# Alarm_clock.net
KiCad netlist of a schematic drawn in EAGLE
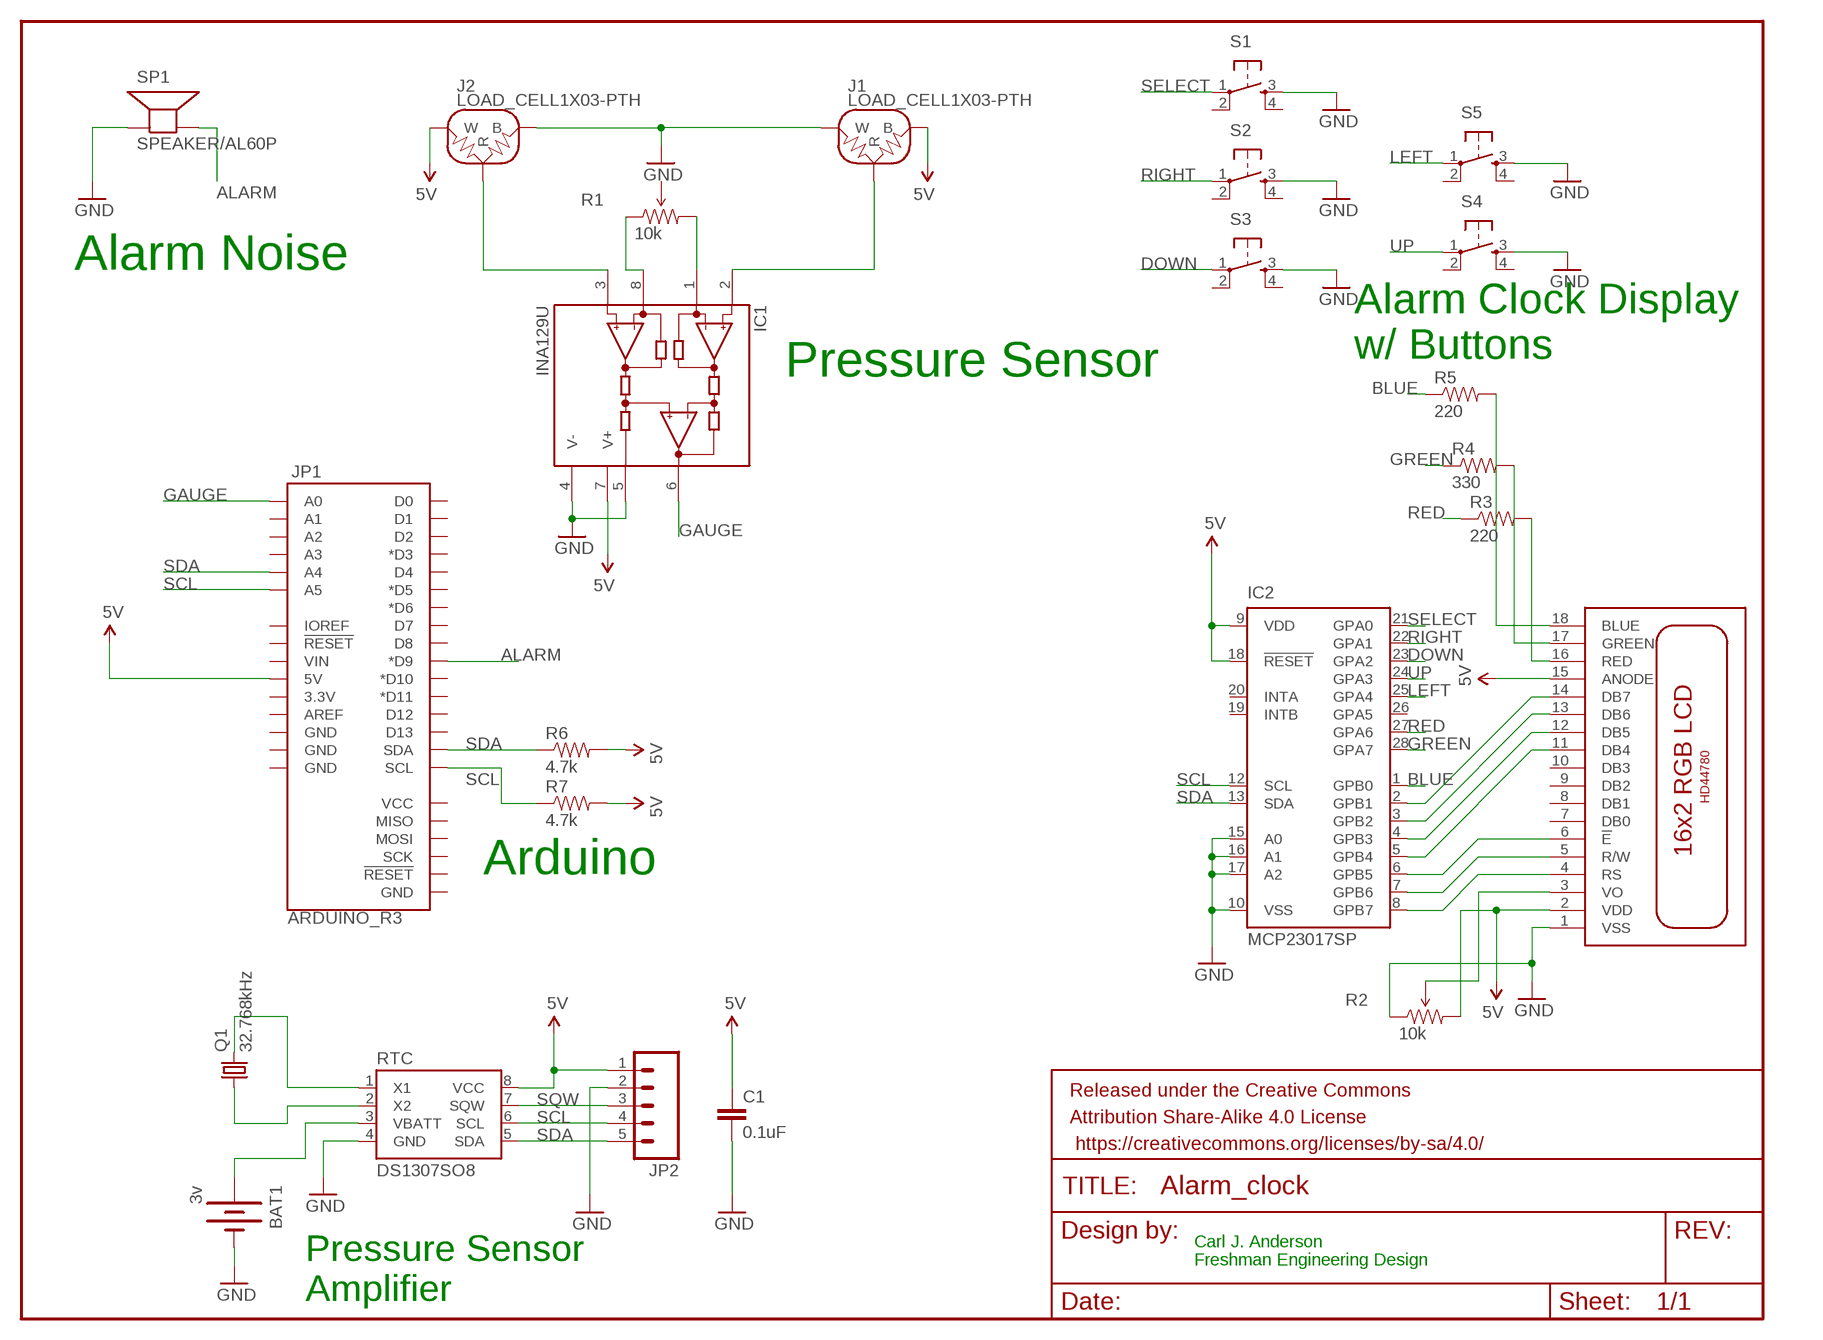
[diagram p0: schematic, sheet 1]

(export (version "E")
  (design (tool "Eeschema 10.0.6"))
  (components
    (comp (ref "BAT1")
      (value "3v")
      (footprint "eagle-import:BATTERY_20MM_PTH_COMPACT")
      (libsource (lib "eagle-import") (part "BATTERYFOB"))
    )
    (comp (ref "C1")
      (value "0.1uF")
      (footprint "eagle-import:0402-CAP")
      (libsource (lib "eagle-import") (part "0.1UF-16V(+-10%)(0402)"))
    )
    (comp (ref "FRAME1")
      (value "FRAME-LETTER")
      (footprint "eagle-import:CREATIVE_COMMONS")
      (libsource (lib "eagle-import") (part "FRAME-LETTER"))
    )
    (comp (ref "IC1")
      (value "INA129U")
      (footprint "eagle-import:SO08")
      (fields (field (name "MF") "TEXAS INSTRUMENTS"))
      (libsource (lib "eagle-import") (part "INA129U"))
    )
    (comp (ref "IC2")
      (value "MCP23017SP")
      (footprint "eagle-import:DIL28-3")
      (fields (field (name "MF") "MICROCHIP") (field (name "MPN") "MCP23017-E/SP"))
      (libsource (lib "eagle-import") (part "MCP23017SP"))
    )
    (comp (ref "J1")
      (value "LOAD_CELL1X03-PTH")
      (footprint "eagle-import:1X03")
      (libsource (lib "eagle-import") (part "LOAD_CELL1X03-PTH"))
    )
    (comp (ref "J2")
      (value "LOAD_CELL1X03-PTH")
      (footprint "eagle-import:1X03")
      (libsource (lib "eagle-import") (part "LOAD_CELL1X03-PTH"))
    )
    (comp (ref "JP1")
      (value "ARDUINO_R3")
      (footprint "eagle-import:ARDUINO_R3")
      (libsource (lib "eagle-import") (part "ARDUINO_R3"))
    )
    (comp (ref "JP2")
      (value "M05PTH")
      (footprint "eagle-import:1X05")
      (libsource (lib "eagle-import") (part "M05PTH"))
    )
    (comp (ref "Q1")
      (value "32.768kHz")
      (footprint "eagle-import:TC26H")
      (libsource (lib "eagle-import") (part "CRYSTALTC26H"))
    )
    (comp (ref "R1")
      (value "10k")
      (footprint "eagle-import:TRIMPOT-5MM-V2")
      (libsource (lib "eagle-import") (part "TRIMPOT"))
    )
    (comp (ref "R2")
      (value "10k")
      (footprint "eagle-import:TRIMPOT-5MM-V2")
      (libsource (lib "eagle-import") (part "TRIMPOT"))
    )
    (comp (ref "R3")
      (value "220")
      (footprint "eagle-import:AXIAL-0.4")
      (libsource (lib "eagle-import") (part "RESISTORPTH-1/4W"))
    )
    (comp (ref "R4")
      (value "330")
      (footprint "eagle-import:AXIAL-0.4")
      (libsource (lib "eagle-import") (part "RESISTORPTH-1/4W"))
    )
    (comp (ref "R5")
      (value "220")
      (footprint "eagle-import:AXIAL-0.4")
      (libsource (lib "eagle-import") (part "RESISTORPTH-1/4W"))
    )
    (comp (ref "R6")
      (value "4.7k")
      (footprint "eagle-import:AXIAL-0.4")
      (libsource (lib "eagle-import") (part "RESISTORPTH-1/4W"))
    )
    (comp (ref "R7")
      (value "4.7k")
      (footprint "eagle-import:AXIAL-0.4")
      (libsource (lib "eagle-import") (part "RESISTORPTH-1/4W"))
    )
    (comp (ref "RTC")
      (value "DS1307SO8")
      (footprint "eagle-import:SO08")
      (libsource (lib "eagle-import") (part "DS1307SO8"))
    )
    (comp (ref "S1")
      (value "TAC_SWITCHPTH")
      (footprint "eagle-import:TACTILE-PTH")
      (libsource (lib "eagle-import") (part "TAC_SWITCHPTH"))
    )
    (comp (ref "S2")
      (value "TAC_SWITCHPTH")
      (footprint "eagle-import:TACTILE-PTH")
      (libsource (lib "eagle-import") (part "TAC_SWITCHPTH"))
    )
    (comp (ref "S3")
      (value "TAC_SWITCHPTH")
      (footprint "eagle-import:TACTILE-PTH")
      (libsource (lib "eagle-import") (part "TAC_SWITCHPTH"))
    )
    (comp (ref "S4")
      (value "TAC_SWITCHPTH")
      (footprint "eagle-import:TACTILE-PTH")
      (libsource (lib "eagle-import") (part "TAC_SWITCHPTH"))
    )
    (comp (ref "S5")
      (value "TAC_SWITCHPTH")
      (footprint "eagle-import:TACTILE-PTH")
      (libsource (lib "eagle-import") (part "TAC_SWITCHPTH"))
    )
    (comp (ref "SP1")
      (value "SPEAKER/AL60P")
      (footprint "eagle-import:AL60P")
      (libsource (lib "eagle-import") (part "SPEAKER/AL60P"))
    )
    (comp (ref "U$1")
      (value "LCD16X2-RGB")
      (footprint "eagle-import:LCD16X2-RGB")
      (libsource (lib "eagle-import") (part "LCD16X2-RGB"))
    )
  )
  (nets
    (net (code "1") (name "/ALARM") (class "Default")
      (node (ref "JP1") (pin "D9") (pinfunction "*D9_D9") (pintype "bidirectional"))
      (node (ref "SP1") (pin "2") (pinfunction "-_2") (pintype "passive"))
    )
    (net (code "2") (name "/BLUE") (class "Default")
      (node (ref "IC2") (pin "1") (pinfunction "GPB0_1") (pintype "bidirectional"))
      (node (ref "R5") (pin "P$1") (pinfunction "1_P$1") (pintype "passive"))
    )
    (net (code "3") (name "/DOWN") (class "Default")
      (node (ref "IC2") (pin "23") (pinfunction "GPA2_23") (pintype "bidirectional"))
      (node (ref "S3") (pin "1") (pinfunction "1_1") (pintype "passive"))
    )
    (net (code "4") (name "/GAUGE") (class "Default")
      (node (ref "IC1") (pin "6") (pinfunction "OUT_6") (pintype "output"))
      (node (ref "JP1") (pin "A0") (pinfunction "A0_A0") (pintype "bidirectional"))
    )
    (net (code "5") (name "/GREEN") (class "Default")
      (node (ref "IC2") (pin "28") (pinfunction "GPA7_28") (pintype "bidirectional"))
      (node (ref "R4") (pin "P$1") (pinfunction "1_P$1") (pintype "passive"))
    )
    (net (code "6") (name "/LEFT") (class "Default")
      (node (ref "IC2") (pin "25") (pinfunction "GPA4_25") (pintype "bidirectional"))
      (node (ref "S5") (pin "1") (pinfunction "1_1") (pintype "passive"))
    )
    (net (code "7") (name "/RED") (class "Default")
      (node (ref "IC2") (pin "27") (pinfunction "GPA6_27") (pintype "bidirectional"))
      (node (ref "R3") (pin "P$1") (pinfunction "1_P$1") (pintype "passive"))
    )
    (net (code "8") (name "/RIGHT") (class "Default")
      (node (ref "IC2") (pin "22") (pinfunction "GPA1_22") (pintype "bidirectional"))
      (node (ref "S2") (pin "1") (pinfunction "1_1") (pintype "passive"))
    )
    (net (code "9") (name "/SCL") (class "Default")
      (node (ref "IC2") (pin "12") (pinfunction "SCL_12") (pintype "input"))
      (node (ref "JP1") (pin "A5") (pinfunction "A5_A5") (pintype "bidirectional"))
      (node (ref "JP1") (pin "SCL") (pinfunction "SCL_SCL") (pintype "bidirectional"))
      (node (ref "JP2") (pin "4") (pinfunction "4_4") (pintype "passive"))
      (node (ref "R7") (pin "P$1") (pinfunction "1_P$1") (pintype "passive"))
      (node (ref "RTC") (pin "6") (pinfunction "SCL_6") (pintype "bidirectional"))
    )
    (net (code "10") (name "/SDA") (class "Default")
      (node (ref "IC2") (pin "13") (pinfunction "SDA_13") (pintype "bidirectional"))
      (node (ref "JP1") (pin "A4") (pinfunction "A4_A4") (pintype "bidirectional"))
      (node (ref "JP1") (pin "SDA") (pinfunction "SDA_SDA") (pintype "bidirectional"))
      (node (ref "JP2") (pin "5") (pinfunction "5_5") (pintype "passive"))
      (node (ref "R6") (pin "P$1") (pinfunction "1_P$1") (pintype "passive"))
      (node (ref "RTC") (pin "5") (pinfunction "SDA_5") (pintype "bidirectional"))
    )
    (net (code "11") (name "/SELECT") (class "Default")
      (node (ref "IC2") (pin "21") (pinfunction "GPA0_21") (pintype "bidirectional"))
      (node (ref "S1") (pin "1") (pinfunction "1_1") (pintype "passive"))
    )
    (net (code "12") (name "/SQW") (class "Default")
      (node (ref "JP2") (pin "3") (pinfunction "3_3") (pintype "passive"))
      (node (ref "RTC") (pin "7") (pinfunction "SQW_7") (pintype "bidirectional"))
    )
    (net (code "13") (name "/UP") (class "Default")
      (node (ref "IC2") (pin "24") (pinfunction "GPA3_24") (pintype "bidirectional"))
      (node (ref "S4") (pin "1") (pinfunction "1_1") (pintype "passive"))
    )
    (net (code "14") (name "5V") (class "Default")
      (node (ref "C1") (pin "1") (pinfunction "1_1") (pintype "passive"))
      (node (ref "IC1") (pin "7") (pinfunction "V+_7") (pintype "power_in"))
      (node (ref "IC2") (pin "18") (pinfunction "~{RESET}_18") (pintype "input"))
      (node (ref "IC2") (pin "9") (pinfunction "VDD_9") (pintype "power_in"))
      (node (ref "J1") (pin "1") (pinfunction "B_1") (pintype "passive"))
      (node (ref "J2") (pin "2") (pinfunction "W_2") (pintype "passive"))
      (node (ref "JP1") (pin "5V") (pinfunction "5V_5V") (pintype "bidirectional"))
      (node (ref "JP2") (pin "1") (pinfunction "1_1") (pintype "passive"))
      (node (ref "R2") (pin "C") (pinfunction "CW_C") (pintype "passive"))
      (node (ref "R6") (pin "P$2") (pinfunction "2_P$2") (pintype "passive"))
      (node (ref "R7") (pin "P$2") (pinfunction "2_P$2") (pintype "passive"))
      (node (ref "RTC") (pin "8") (pinfunction "VCC_8") (pintype "bidirectional"))
      (node (ref "U$1") (pin "15") (pinfunction "ANODE_15") (pintype "bidirectional"))
      (node (ref "U$1") (pin "2") (pinfunction "VDD_2") (pintype "bidirectional"))
    )
    (net (code "15") (name "GND") (class "Default")
      (node (ref "BAT1") (pin "2") (pinfunction "-_2") (pintype "power_in"))
      (node (ref "C1") (pin "2") (pinfunction "2_2") (pintype "passive"))
      (node (ref "IC1") (pin "4") (pinfunction "V-_4") (pintype "power_in"))
      (node (ref "IC1") (pin "5") (pinfunction "REF_5") (pintype "passive"))
      (node (ref "IC2") (pin "10") (pinfunction "VSS_10") (pintype "power_in"))
      (node (ref "IC2") (pin "15") (pinfunction "A0_15") (pintype "input"))
      (node (ref "IC2") (pin "16") (pinfunction "A1_16") (pintype "input"))
      (node (ref "IC2") (pin "17") (pinfunction "A2_17") (pintype "input"))
      (node (ref "J1") (pin "2") (pinfunction "W_2") (pintype "passive"))
      (node (ref "J2") (pin "1") (pinfunction "B_1") (pintype "passive"))
      (node (ref "JP2") (pin "2") (pinfunction "2_2") (pintype "passive"))
      (node (ref "R2") (pin "A") (pinfunction "CCW_A") (pintype "passive"))
      (node (ref "RTC") (pin "4") (pinfunction "GND_4") (pintype "bidirectional"))
      (node (ref "S1") (pin "3") (pinfunction "3_3") (pintype "passive"))
      (node (ref "S2") (pin "3") (pinfunction "3_3") (pintype "passive"))
      (node (ref "S3") (pin "3") (pinfunction "3_3") (pintype "passive"))
      (node (ref "S4") (pin "3") (pinfunction "3_3") (pintype "passive"))
      (node (ref "S5") (pin "3") (pinfunction "3_3") (pintype "passive"))
      (node (ref "SP1") (pin "1") (pinfunction "+_1") (pintype "passive"))
      (node (ref "U$1") (pin "1") (pinfunction "VSS_1") (pintype "bidirectional"))
    )
    (net (code "16") (name "Net-(BAT1-+)") (class "Default")
      (node (ref "BAT1") (pin "1") (pinfunction "+_1") (pintype "power_in"))
      (node (ref "RTC") (pin "3") (pinfunction "VBATT_3") (pintype "bidirectional"))
    )
    (net (code "17") (name "Net-(IC1-+IN)") (class "Default")
      (node (ref "IC1") (pin "3") (pinfunction "+IN_3") (pintype "input"))
      (node (ref "J2") (pin "3") (pinfunction "R_3") (pintype "passive"))
    )
    (net (code "18") (name "Net-(IC1--IN)") (class "Default")
      (node (ref "IC1") (pin "2") (pinfunction "-IN_2") (pintype "input"))
      (node (ref "J1") (pin "3") (pinfunction "R_3") (pintype "passive"))
    )
    (net (code "19") (name "Net-(IC2-GPB1)") (class "Default")
      (node (ref "IC2") (pin "2") (pinfunction "GPB1_2") (pintype "bidirectional"))
      (node (ref "U$1") (pin "14") (pinfunction "DB7_14") (pintype "bidirectional"))
    )
    (net (code "20") (name "Net-(IC2-GPB2)") (class "Default")
      (node (ref "IC2") (pin "3") (pinfunction "GPB2_3") (pintype "bidirectional"))
      (node (ref "U$1") (pin "13") (pinfunction "DB6_13") (pintype "bidirectional"))
    )
    (net (code "21") (name "Net-(IC2-GPB3)") (class "Default")
      (node (ref "IC2") (pin "4") (pinfunction "GPB3_4") (pintype "bidirectional"))
      (node (ref "U$1") (pin "12") (pinfunction "DB5_12") (pintype "bidirectional"))
    )
    (net (code "22") (name "Net-(IC2-GPB4)") (class "Default")
      (node (ref "IC2") (pin "5") (pinfunction "GPB4_5") (pintype "bidirectional"))
      (node (ref "U$1") (pin "11") (pinfunction "DB4_11") (pintype "bidirectional"))
    )
    (net (code "23") (name "Net-(IC2-GPB5)") (class "Default")
      (node (ref "IC2") (pin "6") (pinfunction "GPB5_6") (pintype "bidirectional"))
      (node (ref "U$1") (pin "6") (pinfunction "~{E}_6") (pintype "bidirectional"))
    )
    (net (code "24") (name "Net-(IC2-GPB6)") (class "Default")
      (node (ref "IC2") (pin "7") (pinfunction "GPB6_7") (pintype "bidirectional"))
      (node (ref "U$1") (pin "5") (pinfunction "R/W_5") (pintype "bidirectional"))
    )
    (net (code "25") (name "Net-(IC2-GPB7)") (class "Default")
      (node (ref "IC2") (pin "8") (pinfunction "GPB7_8") (pintype "bidirectional"))
      (node (ref "U$1") (pin "4") (pinfunction "RS_4") (pintype "bidirectional"))
    )
    (net (code "26") (name "Net-(R1-CCW)") (class "Default")
      (node (ref "IC1") (pin "8") (pinfunction "RG_8") (pintype "passive"))
      (node (ref "R1") (pin "A") (pinfunction "CCW_A") (pintype "passive"))
    )
    (net (code "27") (name "Net-(R1-CW)") (class "Default")
      (node (ref "IC1") (pin "1") (pinfunction "RG_1") (pintype "passive"))
      (node (ref "R1") (pin "C") (pinfunction "CW_C") (pintype "passive"))
    )
    (net (code "28") (name "Net-(R2-WIPER)") (class "Default")
      (node (ref "R2") (pin "B") (pinfunction "WIPER_B") (pintype "passive"))
      (node (ref "U$1") (pin "3") (pinfunction "VO_3") (pintype "bidirectional"))
    )
    (net (code "29") (name "Net-(R3-2)") (class "Default")
      (node (ref "R3") (pin "P$2") (pinfunction "2_P$2") (pintype "passive"))
      (node (ref "U$1") (pin "16") (pinfunction "RED_16") (pintype "bidirectional"))
    )
    (net (code "30") (name "Net-(R4-2)") (class "Default")
      (node (ref "R4") (pin "P$2") (pinfunction "2_P$2") (pintype "passive"))
      (node (ref "U$1") (pin "17") (pinfunction "GREEN_17") (pintype "bidirectional"))
    )
    (net (code "31") (name "Net-(R5-2)") (class "Default")
      (node (ref "R5") (pin "P$2") (pinfunction "2_P$2") (pintype "passive"))
      (node (ref "U$1") (pin "18") (pinfunction "BLUE_18") (pintype "bidirectional"))
    )
    (net (code "32") (name "Net-(RTC-X1)") (class "Default")
      (node (ref "Q1") (pin "2") (pinfunction "2_2") (pintype "passive"))
      (node (ref "RTC") (pin "1") (pinfunction "X1_1") (pintype "bidirectional"))
    )
    (net (code "33") (name "Net-(RTC-X2)") (class "Default")
      (node (ref "Q1") (pin "1") (pinfunction "1_1") (pintype "passive"))
      (node (ref "RTC") (pin "2") (pinfunction "X2_2") (pintype "bidirectional"))
    )
    (net (code "34") (name "unconnected-(IC2-GPA5-Pad26)") (class "Default")
      (node (ref "IC2") (pin "26") (pinfunction "GPA5_26") (pintype "bidirectional"))
    )
    (net (code "35") (name "unconnected-(IC2-INTA-Pad20)") (class "Default")
      (node (ref "IC2") (pin "20") (pinfunction "INTA_20") (pintype "output"))
    )
    (net (code "36") (name "unconnected-(IC2-INTB-Pad19)") (class "Default")
      (node (ref "IC2") (pin "19") (pinfunction "INTB_19") (pintype "output"))
    )
    (net (code "37") (name "unconnected-(JP1-*D3-PadD3)") (class "Default")
      (node (ref "JP1") (pin "D3") (pinfunction "*D3_D3") (pintype "bidirectional"))
    )
    (net (code "38") (name "unconnected-(JP1-*D5-PadD5)") (class "Default")
      (node (ref "JP1") (pin "D5") (pinfunction "*D5_D5") (pintype "bidirectional"))
    )
    (net (code "39") (name "unconnected-(JP1-*D6-PadD6)") (class "Default")
      (node (ref "JP1") (pin "D6") (pinfunction "*D6_D6") (pintype "bidirectional"))
    )
    (net (code "40") (name "unconnected-(JP1-*D10-PadD10)") (class "Default")
      (node (ref "JP1") (pin "D10") (pinfunction "*D10_D10") (pintype "bidirectional"))
    )
    (net (code "41") (name "unconnected-(JP1-*D11-PadD11)") (class "Default")
      (node (ref "JP1") (pin "D11") (pinfunction "*D11_D11") (pintype "bidirectional"))
    )
    (net (code "42") (name "unconnected-(JP1-GND-PadGND@1)") (class "Default")
      (node (ref "JP1") (pin "GND@1") (pinfunction "GND_GND@1") (pintype "bidirectional"))
    )
    (net (code "43") (name "unconnected-(JP1-GND-PadGND@2)") (class "Default")
      (node (ref "JP1") (pin "GND@2") (pinfunction "GND_GND@2") (pintype "bidirectional"))
    )
    (net (code "44") (name "unconnected-(JP1-GND-PadGND@3)") (class "Default")
      (node (ref "JP1") (pin "GND@3") (pinfunction "GND_GND@3") (pintype "bidirectional"))
    )
    (net (code "45") (name "unconnected-(JP1-GND-PadGND@4)") (class "Default")
      (node (ref "JP1") (pin "GND@4") (pinfunction "GND_GND@4") (pintype "bidirectional"))
    )
    (net (code "46") (name "unconnected-(JP1-Pad3.3V)") (class "Default")
      (node (ref "JP1") (pin "3.3V") (pinfunction "3.3V_3.3V") (pintype "bidirectional"))
    )
    (net (code "47") (name "unconnected-(JP1-PadA1)") (class "Default")
      (node (ref "JP1") (pin "A1") (pinfunction "A1_A1") (pintype "bidirectional"))
    )
    (net (code "48") (name "unconnected-(JP1-PadA2)") (class "Default")
      (node (ref "JP1") (pin "A2") (pinfunction "A2_A2") (pintype "bidirectional"))
    )
    (net (code "49") (name "unconnected-(JP1-PadA3)") (class "Default")
      (node (ref "JP1") (pin "A3") (pinfunction "A3_A3") (pintype "bidirectional"))
    )
    (net (code "50") (name "unconnected-(JP1-PadAREF)") (class "Default")
      (node (ref "JP1") (pin "AREF") (pinfunction "AREF_AREF") (pintype "bidirectional"))
    )
    (net (code "51") (name "unconnected-(JP1-PadD0)") (class "Default")
      (node (ref "JP1") (pin "D0") (pinfunction "D0_D0") (pintype "bidirectional"))
    )
    (net (code "52") (name "unconnected-(JP1-PadD1)") (class "Default")
      (node (ref "JP1") (pin "D1") (pinfunction "D1_D1") (pintype "bidirectional"))
    )
    (net (code "53") (name "unconnected-(JP1-PadD2)") (class "Default")
      (node (ref "JP1") (pin "D2") (pinfunction "D2_D2") (pintype "bidirectional"))
    )
    (net (code "54") (name "unconnected-(JP1-PadD4)") (class "Default")
      (node (ref "JP1") (pin "D4") (pinfunction "D4_D4") (pintype "bidirectional"))
    )
    (net (code "55") (name "unconnected-(JP1-PadD7)") (class "Default")
      (node (ref "JP1") (pin "D7") (pinfunction "D7_D7") (pintype "bidirectional"))
    )
    (net (code "56") (name "unconnected-(JP1-PadD8)") (class "Default")
      (node (ref "JP1") (pin "D8") (pinfunction "D8_D8") (pintype "bidirectional"))
    )
    (net (code "57") (name "unconnected-(JP1-PadD12)") (class "Default")
      (node (ref "JP1") (pin "D12") (pinfunction "D12_D12") (pintype "bidirectional"))
    )
    (net (code "58") (name "unconnected-(JP1-PadD13)") (class "Default")
      (node (ref "JP1") (pin "D13") (pinfunction "D13_D13") (pintype "bidirectional"))
    )
    (net (code "59") (name "unconnected-(JP1-PadIOREF)") (class "Default")
      (node (ref "JP1") (pin "IOREF") (pinfunction "IOREF_IOREF") (pintype "bidirectional"))
    )
    (net (code "60") (name "unconnected-(JP1-PadMISO)") (class "Default")
      (node (ref "JP1") (pin "MISO") (pinfunction "MISO_MISO") (pintype "bidirectional"))
    )
    (net (code "61") (name "unconnected-(JP1-PadMOSI)") (class "Default")
      (node (ref "JP1") (pin "MOSI") (pinfunction "MOSI_MOSI") (pintype "bidirectional"))
    )
    (net (code "62") (name "unconnected-(JP1-PadSCK)") (class "Default")
      (node (ref "JP1") (pin "SCK") (pinfunction "SCK_SCK") (pintype "bidirectional"))
    )
    (net (code "63") (name "unconnected-(JP1-PadVCC)") (class "Default")
      (node (ref "JP1") (pin "VCC") (pinfunction "VCC_VCC") (pintype "bidirectional"))
    )
    (net (code "64") (name "unconnected-(JP1-PadVIN)") (class "Default")
      (node (ref "JP1") (pin "VIN") (pinfunction "VIN_VIN") (pintype "bidirectional"))
    )
    (net (code "65") (name "unconnected-(JP1-~{RESET}-PadRESET@1)") (class "Default")
      (node (ref "JP1") (pin "RESET@1") (pinfunction "~{RESET}_RESET@1") (pintype "bidirectional"))
    )
    (net (code "66") (name "unconnected-(JP1-~{RESET}-PadRESET@2)") (class "Default")
      (node (ref "JP1") (pin "RESET@2") (pinfunction "~{RESET}_RESET@2") (pintype "bidirectional"))
    )
    (net (code "67") (name "unconnected-(R1-WIPER-PadB)") (class "Default")
      (node (ref "R1") (pin "B") (pinfunction "WIPER_B") (pintype "passive"))
    )
    (net (code "68") (name "unconnected-(S1-Pad2)") (class "Default")
      (node (ref "S1") (pin "2") (pinfunction "2_2") (pintype "passive"))
    )
    (net (code "69") (name "unconnected-(S1-Pad4)") (class "Default")
      (node (ref "S1") (pin "4") (pinfunction "4_4") (pintype "passive"))
    )
    (net (code "70") (name "unconnected-(S2-Pad2)") (class "Default")
      (node (ref "S2") (pin "2") (pinfunction "2_2") (pintype "passive"))
    )
    (net (code "71") (name "unconnected-(S2-Pad4)") (class "Default")
      (node (ref "S2") (pin "4") (pinfunction "4_4") (pintype "passive"))
    )
    (net (code "72") (name "unconnected-(S3-Pad2)") (class "Default")
      (node (ref "S3") (pin "2") (pinfunction "2_2") (pintype "passive"))
    )
    (net (code "73") (name "unconnected-(S3-Pad4)") (class "Default")
      (node (ref "S3") (pin "4") (pinfunction "4_4") (pintype "passive"))
    )
    (net (code "74") (name "unconnected-(S4-Pad2)") (class "Default")
      (node (ref "S4") (pin "2") (pinfunction "2_2") (pintype "passive"))
    )
    (net (code "75") (name "unconnected-(S4-Pad4)") (class "Default")
      (node (ref "S4") (pin "4") (pinfunction "4_4") (pintype "passive"))
    )
    (net (code "76") (name "unconnected-(S5-Pad2)") (class "Default")
      (node (ref "S5") (pin "2") (pinfunction "2_2") (pintype "passive"))
    )
    (net (code "77") (name "unconnected-(S5-Pad4)") (class "Default")
      (node (ref "S5") (pin "4") (pinfunction "4_4") (pintype "passive"))
    )
    (net (code "78") (name "unconnected-(U$1-DB0-Pad7)") (class "Default")
      (node (ref "U$1") (pin "7") (pinfunction "DB0_7") (pintype "bidirectional"))
    )
    (net (code "79") (name "unconnected-(U$1-DB1-Pad8)") (class "Default")
      (node (ref "U$1") (pin "8") (pinfunction "DB1_8") (pintype "bidirectional"))
    )
    (net (code "80") (name "unconnected-(U$1-DB2-Pad9)") (class "Default")
      (node (ref "U$1") (pin "9") (pinfunction "DB2_9") (pintype "bidirectional"))
    )
    (net (code "81") (name "unconnected-(U$1-DB3-Pad10)") (class "Default")
      (node (ref "U$1") (pin "10") (pinfunction "DB3_10") (pintype "bidirectional"))
    )
  )
)
